# Tone_board.net
KiCad netlist of a schematic drawn in Altium Designer
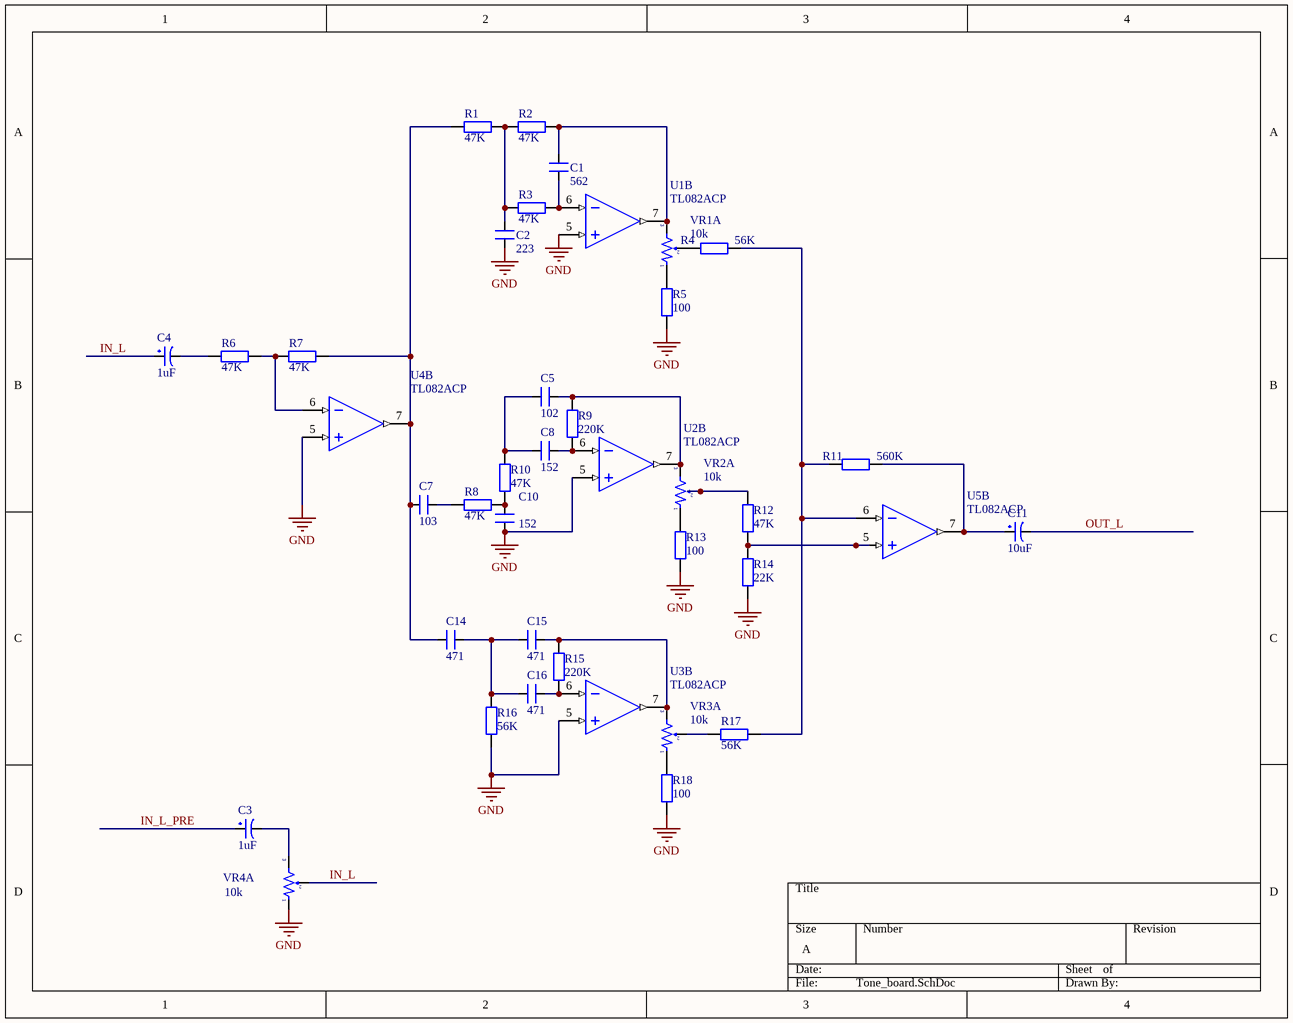
[diagram p0: Tone_board.SchDoc]

(export (version "E")
  (design (tool "Eeschema 10.0.6"))
  (components
    (comp (ref "C1")
      (value "562")
      (footprint "WIMA-FKP-2-1nF")
      (libsource (lib "MH_DA_THU_VIEN_16122016") (part "TU_MICA_ 104 100V(2A104J)_MH"))
    )
    (comp (ref "C2")
      (value "223")
      (footprint "WIMA-FKP-2-1nF")
      (libsource (lib "MH_DA_THU_VIEN_16122016") (part "TU_MICA_ 104 100V(2A104J)_MH"))
    )
    (comp (ref "C3")
      (value "1uF")
      (footprint "CP1/3.0")
      (description "TU_HOA_4.7uF_100V_MH")
      (libsource (lib "MH_DA_THU_VIEN_16122016") (part "TU_HOA_4.7uF_100V_MH"))
    )
    (comp (ref "C4")
      (value "1uF")
      (footprint "CP1/3.0")
      (description "TU_HOA_4.7uF_100V_MH")
      (libsource (lib "MH_DA_THU_VIEN_16122016") (part "TU_HOA_4.7uF_100V_MH"))
    )
    (comp (ref "C5")
      (value "102")
      (footprint "WIMA-FKP-2-1nF")
      (libsource (lib "MH_DA_THU_VIEN_16122016") (part "TU_MICA_ 104 100V(2A104J)_MH"))
    )
    (comp (ref "C7")
      (value "103")
      (footprint "WIMA-FKP-2-1nF")
      (libsource (lib "MH_DA_THU_VIEN_16122016") (part "TU_MICA_ 104 100V(2A104J)_MH"))
    )
    (comp (ref "C8")
      (value "152")
      (footprint "WIMA-FKP-2-1nF")
      (libsource (lib "MH_DA_THU_VIEN_16122016") (part "TU_MICA_ 104 100V(2A104J)_MH"))
    )
    (comp (ref "C10")
      (value "152")
      (footprint "WIMA-FKP-2-1nF")
      (libsource (lib "MH_DA_THU_VIEN_16122016") (part "TU_MICA_ 104 100V(2A104J)_MH"))
    )
    (comp (ref "C11")
      (value "10uF")
      (footprint "CP1/3.0")
      (description "TU_HOA_4.7uF_100V_MH")
      (libsource (lib "MH_DA_THU_VIEN_16122016") (part "TU_HOA_4.7uF_100V_MH"))
    )
    (comp (ref "C14")
      (value "471")
      (footprint "WIMA-FKP-2-1nF")
      (libsource (lib "MH_DA_THU_VIEN_16122016") (part "TU_MICA_ 104 100V(2A104J)_MH"))
    )
    (comp (ref "C15")
      (value "471")
      (footprint "WIMA-FKP-2-1nF")
      (libsource (lib "MH_DA_THU_VIEN_16122016") (part "TU_MICA_ 104 100V(2A104J)_MH"))
    )
    (comp (ref "C16")
      (value "471")
      (footprint "WIMA-FKP-2-1nF")
      (libsource (lib "MH_DA_THU_VIEN_16122016") (part "TU_MICA_ 104 100V(2A104J)_MH"))
    )
    (comp (ref "R1")
      (value "47K")
      (footprint "TRO_VACH_ 1/4W")
      (description "Resistor")
      (fields (field (name "PUBLISHER") "Altium Limited"))
      (libsource (lib "") (part "TRO_VACH_1/2W_MH_1"))
    )
    (comp (ref "R2")
      (value "47K")
      (footprint "TRO_VACH_ 1/4W")
      (description "Resistor")
      (fields (field (name "PUBLISHER") "Altium Limited"))
      (libsource (lib "") (part "TRO_VACH_1/2W_MH_1"))
    )
    (comp (ref "R3")
      (value "47K")
      (footprint "TRO_VACH_ 1/4W")
      (description "Resistor")
      (fields (field (name "PUBLISHER") "Altium Limited"))
      (libsource (lib "") (part "TRO_VACH_1/2W_MH_1"))
    )
    (comp (ref "R4")
      (value "56K")
      (footprint "TRO_VACH_ 1/4W")
      (description "Resistor")
      (fields (field (name "PUBLISHER") "Altium Limited"))
      (libsource (lib "") (part "TRO_VACH_1/2W_MH_3"))
    )
    (comp (ref "R5")
      (value "100")
      (footprint "TRO_VACH_ 1/4W")
      (description "Resistor")
      (fields (field (name "PUBLISHER") "Altium Limited"))
      (libsource (lib "") (part "TRO_VACH_1/2W_MH_2"))
    )
    (comp (ref "R6")
      (value "47K")
      (footprint "TRO_VACH_ 1/4W")
      (description "Resistor")
      (fields (field (name "PUBLISHER") "Altium Limited"))
      (libsource (lib "") (part "TRO_VACH_1/2W_MH_1"))
    )
    (comp (ref "R7")
      (value "47K")
      (footprint "TRO_VACH_ 1/4W")
      (description "Resistor")
      (fields (field (name "PUBLISHER") "Altium Limited"))
      (libsource (lib "") (part "TRO_VACH_1/2W_MH_1"))
    )
    (comp (ref "R8")
      (value "47K")
      (footprint "TRO_VACH_ 1/4W")
      (description "Resistor")
      (fields (field (name "PUBLISHER") "Altium Limited"))
      (libsource (lib "") (part "TRO_VACH_1/2W_MH_3"))
    )
    (comp (ref "R9")
      (value "220K")
      (footprint "TRO_VACH_ 1/4W")
      (description "Resistor")
      (fields (field (name "PUBLISHER") "Altium Limited"))
      (libsource (lib "") (part "TRO_VACH_1/2W_MH_2"))
    )
    (comp (ref "R10")
      (value "47K")
      (footprint "TRO_VACH_ 1/4W")
      (description "Resistor")
      (fields (field (name "PUBLISHER") "Altium Limited"))
      (libsource (lib "MH_DA_THU_VIEN_16122016") (part "TRO_VACH_1/2W_MH"))
    )
    (comp (ref "R11")
      (value "560K")
      (footprint "TRO_VACH_ 1/4W")
      (description "Resistor")
      (fields (field (name "PUBLISHER") "Altium Limited"))
      (libsource (lib "") (part "TRO_VACH_1/2W_MH_3"))
    )
    (comp (ref "R12")
      (value "47K")
      (footprint "TRO_VACH_ 1/4W")
      (description "Resistor")
      (fields (field (name "PUBLISHER") "Altium Limited"))
      (libsource (lib "") (part "TRO_VACH_1/2W_MH_2"))
    )
    (comp (ref "R13")
      (value "100")
      (footprint "TRO_VACH_ 1/4W")
      (description "Resistor")
      (fields (field (name "PUBLISHER") "Altium Limited"))
      (libsource (lib "") (part "TRO_VACH_1/2W_MH_2"))
    )
    (comp (ref "R14")
      (value "22K")
      (footprint "TRO_VACH_ 1/4W")
      (description "Resistor")
      (fields (field (name "PUBLISHER") "Altium Limited"))
      (libsource (lib "") (part "TRO_VACH_1/2W_MH_2"))
    )
    (comp (ref "R15")
      (value "220K")
      (footprint "TRO_VACH_ 1/4W")
      (description "Resistor")
      (fields (field (name "PUBLISHER") "Altium Limited"))
      (libsource (lib "") (part "TRO_VACH_1/2W_MH_2"))
    )
    (comp (ref "R16")
      (value "56K")
      (footprint "TRO_VACH_ 1/4W")
      (description "Resistor")
      (fields (field (name "PUBLISHER") "Altium Limited"))
      (libsource (lib "") (part "TRO_VACH_1/2W_MH_2"))
    )
    (comp (ref "R17")
      (value "56K")
      (footprint "TRO_VACH_ 1/4W")
      (description "Resistor")
      (fields (field (name "PUBLISHER") "Altium Limited"))
      (libsource (lib "") (part "TRO_VACH_1/2W_MH_3"))
    )
    (comp (ref "R18")
      (value "100")
      (footprint "TRO_VACH_ 1/4W")
      (description "Resistor")
      (fields (field (name "PUBLISHER") "Altium Limited"))
      (libsource (lib "") (part "TRO_VACH_1/2W_MH_2"))
    )
    (comp (ref "U1")
      (value "TL082ACP")
      (footprint "DIP8")
      (description "JFET-Input Operational Amplifier")
      (fields (field (name "PUBLISHER") "Altium Limited"))
      (libsource (lib "Schlib1") (part "TL082ACP"))
    )
    (comp (ref "U2")
      (value "TL082ACP")
      (footprint "DIP8")
      (description "JFET-Input Operational Amplifier")
      (fields (field (name "PUBLISHER") "Altium Limited"))
      (libsource (lib "Schlib1") (part "TL082ACP"))
    )
    (comp (ref "U3")
      (value "TL082ACP")
      (footprint "DIP8")
      (description "JFET-Input Operational Amplifier")
      (fields (field (name "PUBLISHER") "Altium Limited"))
      (libsource (lib "Schlib1") (part "TL082ACP"))
    )
    (comp (ref "U4")
      (value "TL082ACP")
      (footprint "DIP8")
      (description "JFET-Input Operational Amplifier")
      (fields (field (name "PUBLISHER") "Altium Limited"))
      (libsource (lib "Schlib1") (part "TL082ACP"))
    )
    (comp (ref "U5")
      (value "TL082ACP")
      (footprint "DIP8")
      (description "JFET-Input Operational Amplifier")
      (fields (field (name "PUBLISHER") "Altium Limited"))
      (libsource (lib "Schlib1") (part "TL082ACP"))
    )
    (comp (ref "VR1")
      (value "10k")
      (footprint "9011")
      (description "Triet Ap Doi 10k")
      (libsource (lib "Schlib1") (part "Triet Ap Doi 10k_MH"))
    )
    (comp (ref "VR2")
      (value "10k")
      (footprint "9011")
      (description "Triet Ap Doi 10k")
      (libsource (lib "Schlib1") (part "Triet Ap Doi 10k_MH"))
    )
    (comp (ref "VR3")
      (value "10k")
      (footprint "9011")
      (description "Triet Ap Doi 10k")
      (libsource (lib "Schlib1") (part "Triet Ap Doi 10k_MH"))
    )
    (comp (ref "VR4")
      (value "10k")
      (footprint "9011")
      (description "Triet Ap Doi 10k")
      (libsource (lib "Schlib1") (part "Triet Ap Doi 10k_MH"))
    )
  )
  (nets
    (net (code "1") (name "/IN_L") (class "Default")
      (node (ref "C4") (pin "1") (pinfunction "1_1") (pintype "passive"))
      (node (ref "VR4") (pin "2") (pinfunction "2_2") (pintype "passive"))
    )
    (net (code "2") (name "/IN_L_PRE") (class "Default")
      (node (ref "C3") (pin "1") (pinfunction "1_1") (pintype "passive"))
    )
    (net (code "3") (name "/OUT_L") (class "Default")
      (node (ref "C11") (pin "2") (pinfunction "2_2") (pintype "passive"))
    )
    (net (code "4") (name "GND") (class "Default")
      (node (ref "C10") (pin "2") (pinfunction "2_2") (pintype "passive"))
      (node (ref "C2") (pin "1") (pinfunction "1_1") (pintype "passive"))
      (node (ref "R13") (pin "1") (pinfunction "1_1") (pintype "passive"))
      (node (ref "R14") (pin "1") (pinfunction "1_1") (pintype "passive"))
      (node (ref "R16") (pin "1") (pinfunction "1_1") (pintype "passive"))
      (node (ref "R18") (pin "1") (pinfunction "1_1") (pintype "passive"))
      (node (ref "R5") (pin "1") (pinfunction "1_1") (pintype "passive"))
      (node (ref "U1") (pin "5") (pinfunction "IN+_5") (pintype "input"))
      (node (ref "U2") (pin "5") (pinfunction "IN+_5") (pintype "input"))
      (node (ref "U3") (pin "5") (pinfunction "IN+_5") (pintype "input"))
      (node (ref "U4") (pin "5") (pinfunction "IN+_5") (pintype "input"))
      (node (ref "VR4") (pin "1") (pinfunction "1_1") (pintype "passive"))
    )
    (net (code "5") (name "Net-(C2-Pad2)") (class "Default")
      (node (ref "C2") (pin "2") (pinfunction "2_2") (pintype "passive"))
      (node (ref "R1") (pin "2") (pinfunction "2_2") (pintype "passive"))
      (node (ref "R2") (pin "1") (pinfunction "1_1") (pintype "passive"))
      (node (ref "R3") (pin "1") (pinfunction "1_1") (pintype "passive"))
    )
    (net (code "6") (name "Net-(C3-Pad2)") (class "Default")
      (node (ref "C3") (pin "2") (pinfunction "2_2") (pintype "passive"))
      (node (ref "VR4") (pin "3") (pinfunction "3_3") (pintype "passive"))
    )
    (net (code "7") (name "Net-(C4-Pad2)") (class "Default")
      (node (ref "C4") (pin "2") (pinfunction "2_2") (pintype "passive"))
      (node (ref "R6") (pin "1") (pinfunction "1_1") (pintype "passive"))
    )
    (net (code "8") (name "Net-(C5-Pad2)") (class "Default")
      (node (ref "C5") (pin "2") (pinfunction "2_2") (pintype "passive"))
      (node (ref "C8") (pin "2") (pinfunction "2_2") (pintype "passive"))
      (node (ref "R10") (pin "1") (pinfunction "1_1") (pintype "passive"))
    )
    (net (code "9") (name "Net-(C7-Pad2)") (class "Default")
      (node (ref "C7") (pin "2") (pinfunction "2_2") (pintype "passive"))
      (node (ref "R8") (pin "2") (pinfunction "2_2") (pintype "passive"))
    )
    (net (code "10") (name "Net-(C10-Pad1)") (class "Default")
      (node (ref "C10") (pin "1") (pinfunction "1_1") (pintype "passive"))
      (node (ref "R10") (pin "2") (pinfunction "2_2") (pintype "passive"))
      (node (ref "R8") (pin "1") (pinfunction "1_1") (pintype "passive"))
    )
    (net (code "11") (name "Net-(C14-Pad1)") (class "Default")
      (node (ref "C14") (pin "1") (pinfunction "1_1") (pintype "passive"))
      (node (ref "C15") (pin "2") (pinfunction "2_2") (pintype "passive"))
      (node (ref "C16") (pin "2") (pinfunction "2_2") (pintype "passive"))
      (node (ref "R16") (pin "2") (pinfunction "2_2") (pintype "passive"))
    )
    (net (code "12") (name "Net-(R4-Pad2)") (class "Default")
      (node (ref "R4") (pin "2") (pinfunction "2_2") (pintype "passive"))
      (node (ref "VR1") (pin "2") (pinfunction "2_2") (pintype "passive"))
    )
    (net (code "13") (name "Net-(R5-Pad2)") (class "Default")
      (node (ref "R5") (pin "2") (pinfunction "2_2") (pintype "passive"))
      (node (ref "VR1") (pin "1") (pinfunction "1_1") (pintype "passive"))
    )
    (net (code "14") (name "Net-(R12-Pad2)") (class "Default")
      (node (ref "R12") (pin "2") (pinfunction "2_2") (pintype "passive"))
      (node (ref "VR2") (pin "2") (pinfunction "2_2") (pintype "passive"))
    )
    (net (code "15") (name "Net-(R13-Pad2)") (class "Default")
      (node (ref "R13") (pin "2") (pinfunction "2_2") (pintype "passive"))
      (node (ref "VR2") (pin "1") (pinfunction "1_1") (pintype "passive"))
    )
    (net (code "16") (name "Net-(R17-Pad2)") (class "Default")
      (node (ref "R17") (pin "2") (pinfunction "2_2") (pintype "passive"))
      (node (ref "VR3") (pin "2") (pinfunction "2_2") (pintype "passive"))
    )
    (net (code "17") (name "Net-(R18-Pad2)") (class "Default")
      (node (ref "R18") (pin "2") (pinfunction "2_2") (pintype "passive"))
      (node (ref "VR3") (pin "1") (pinfunction "1_1") (pintype "passive"))
    )
    (net (code "18") (name "Net-(U1B-IN-)") (class "Default")
      (node (ref "C1") (pin "1") (pinfunction "1_1") (pintype "passive"))
      (node (ref "R3") (pin "2") (pinfunction "2_2") (pintype "passive"))
      (node (ref "U1") (pin "6") (pinfunction "IN-_6") (pintype "input"))
    )
    (net (code "19") (name "Net-(U1B-OUT)") (class "Default")
      (node (ref "C1") (pin "2") (pinfunction "2_2") (pintype "passive"))
      (node (ref "R2") (pin "2") (pinfunction "2_2") (pintype "passive"))
      (node (ref "U1") (pin "7") (pinfunction "OUT_7") (pintype "output"))
      (node (ref "VR1") (pin "3") (pinfunction "3_3") (pintype "passive"))
    )
    (net (code "20") (name "Net-(U2B-IN-)") (class "Default")
      (node (ref "C8") (pin "1") (pinfunction "1_1") (pintype "passive"))
      (node (ref "R9") (pin "1") (pinfunction "1_1") (pintype "passive"))
      (node (ref "U2") (pin "6") (pinfunction "IN-_6") (pintype "input"))
    )
    (net (code "21") (name "Net-(U2B-OUT)") (class "Default")
      (node (ref "C5") (pin "1") (pinfunction "1_1") (pintype "passive"))
      (node (ref "R9") (pin "2") (pinfunction "2_2") (pintype "passive"))
      (node (ref "U2") (pin "7") (pinfunction "OUT_7") (pintype "output"))
      (node (ref "VR2") (pin "3") (pinfunction "3_3") (pintype "passive"))
    )
    (net (code "22") (name "Net-(U3B-IN-)") (class "Default")
      (node (ref "C16") (pin "1") (pinfunction "1_1") (pintype "passive"))
      (node (ref "R15") (pin "1") (pinfunction "1_1") (pintype "passive"))
      (node (ref "U3") (pin "6") (pinfunction "IN-_6") (pintype "input"))
    )
    (net (code "23") (name "Net-(U3B-OUT)") (class "Default")
      (node (ref "C15") (pin "1") (pinfunction "1_1") (pintype "passive"))
      (node (ref "R15") (pin "2") (pinfunction "2_2") (pintype "passive"))
      (node (ref "U3") (pin "7") (pinfunction "OUT_7") (pintype "output"))
      (node (ref "VR3") (pin "3") (pinfunction "3_3") (pintype "passive"))
    )
    (net (code "24") (name "Net-(U4B-IN-)") (class "Default")
      (node (ref "R6") (pin "2") (pinfunction "2_2") (pintype "passive"))
      (node (ref "R7") (pin "1") (pinfunction "1_1") (pintype "passive"))
      (node (ref "U4") (pin "6") (pinfunction "IN-_6") (pintype "input"))
    )
    (net (code "25") (name "Net-(U4B-OUT)") (class "Default")
      (node (ref "C14") (pin "2") (pinfunction "2_2") (pintype "passive"))
      (node (ref "C7") (pin "1") (pinfunction "1_1") (pintype "passive"))
      (node (ref "R1") (pin "1") (pinfunction "1_1") (pintype "passive"))
      (node (ref "R7") (pin "2") (pinfunction "2_2") (pintype "passive"))
      (node (ref "U4") (pin "7") (pinfunction "OUT_7") (pintype "output"))
    )
    (net (code "26") (name "Net-(U5B-IN+)") (class "Default")
      (node (ref "R12") (pin "1") (pinfunction "1_1") (pintype "passive"))
      (node (ref "R14") (pin "2") (pinfunction "2_2") (pintype "passive"))
      (node (ref "U5") (pin "5") (pinfunction "IN+_5") (pintype "input"))
    )
    (net (code "27") (name "Net-(U5B-IN-)") (class "Default")
      (node (ref "R11") (pin "2") (pinfunction "2_2") (pintype "passive"))
      (node (ref "R17") (pin "1") (pinfunction "1_1") (pintype "passive"))
      (node (ref "R4") (pin "1") (pinfunction "1_1") (pintype "passive"))
      (node (ref "U5") (pin "6") (pinfunction "IN-_6") (pintype "input"))
    )
    (net (code "28") (name "Net-(U5B-OUT)") (class "Default")
      (node (ref "C11") (pin "1") (pinfunction "1_1") (pintype "passive"))
      (node (ref "R11") (pin "1") (pinfunction "1_1") (pintype "passive"))
      (node (ref "U5") (pin "7") (pinfunction "OUT_7") (pintype "output"))
    )
  )
)
